# ProPrj__-_AI__2025-12-12.net
KiCad netlist of a schematic drawn in EasyEDA Pro
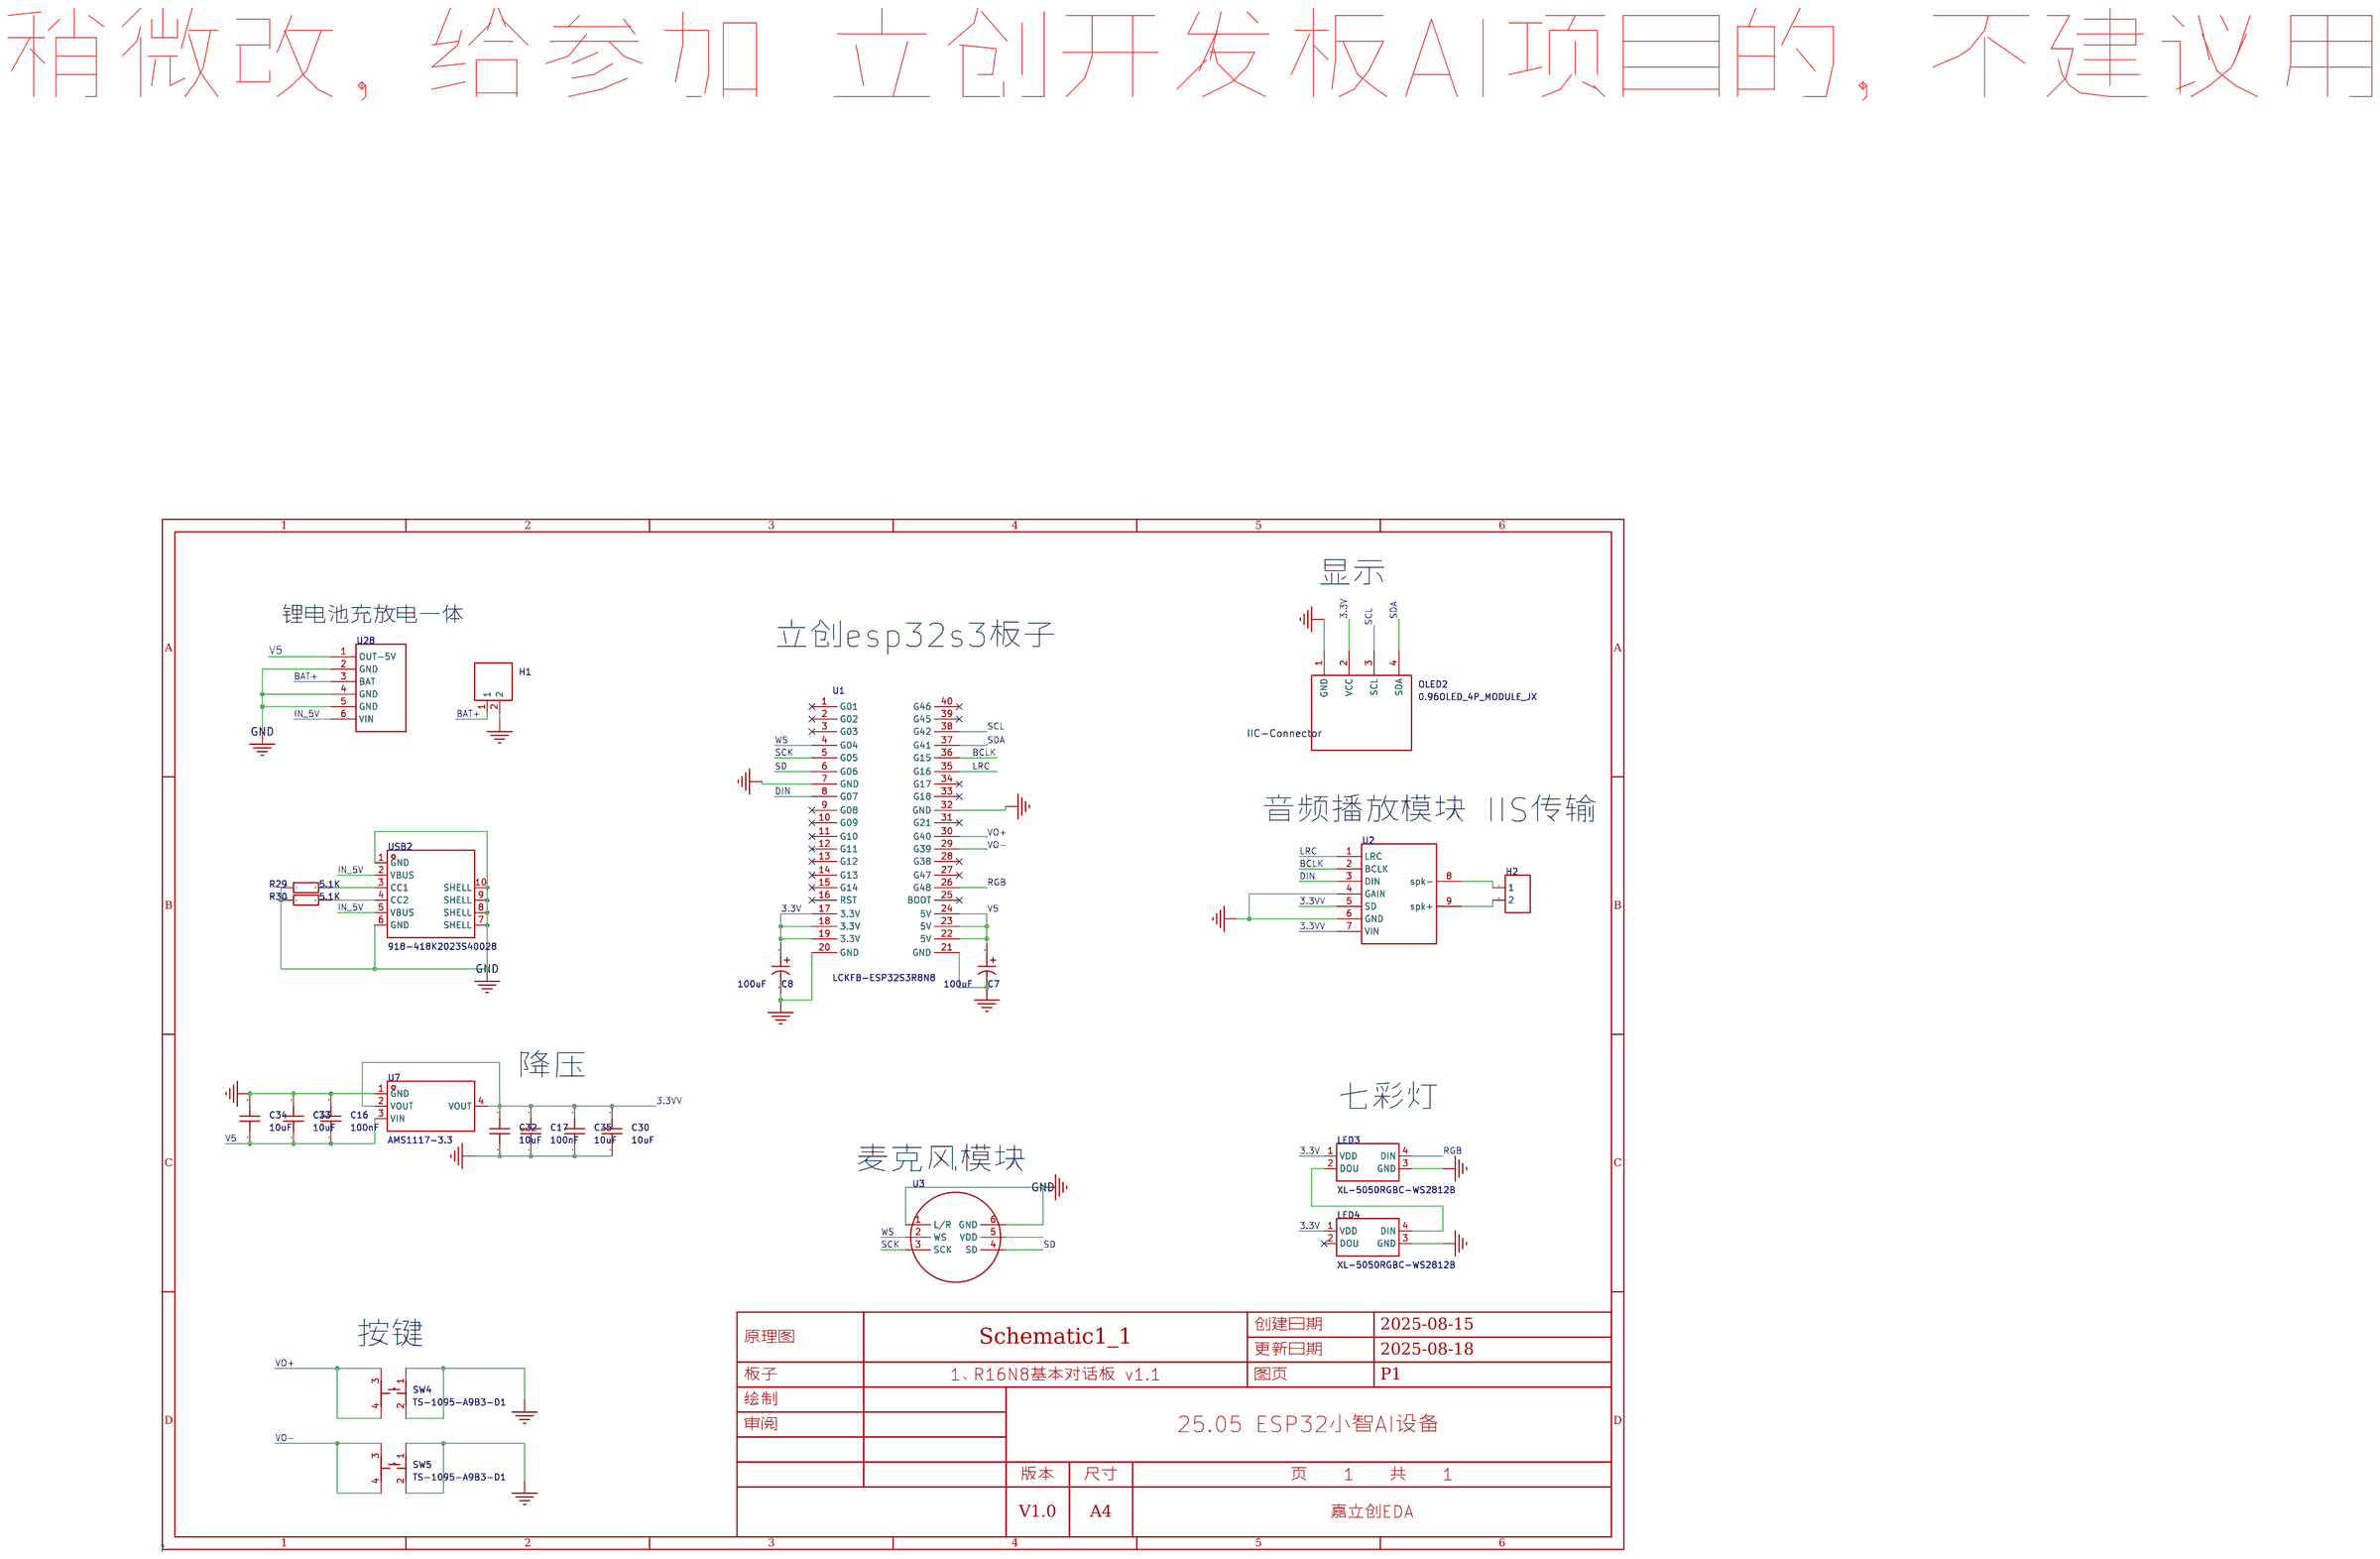
[diagram p0: schematic sheet]

(export (version "E")
  (design (tool "Eeschema 10.0.6"))
  (components
    (comp (ref "C7")
      (value "100uF")
      (footprint "easyedapro:CAP-SMD_BD6.3-L6.6-W6.6-LS7.6-RD")
      (fields (field (name "Manufacturer Part") "RVT1H101M0607") (field (name "Manufacturer") "ROQANG(容强)"))
      (libsource (lib "easyedapro") (part "RVT1H101M0607"))
    )
    (comp (ref "C8")
      (value "100uF")
      (footprint "easyedapro:CAP-SMD_BD6.3-L6.6-W6.6-LS7.6-RD")
      (fields (field (name "Manufacturer Part") "RVT1H101M0607") (field (name "Manufacturer") "ROQANG(容强)"))
      (libsource (lib "easyedapro") (part "RVT1H101M0607"))
    )
    (comp (ref "C16")
      (value "100nF")
      (footprint "easyedapro:C0603")
      (libsource (lib "easyedapro") (part "CapAcitance"))
    )
    (comp (ref "C17")
      (value "100nF")
      (footprint "easyedapro:C0603")
      (libsource (lib "easyedapro") (part "CapAcitance"))
    )
    (comp (ref "C30")
      (value "10uF")
      (footprint "easyedapro:C0603")
      (libsource (lib "easyedapro") (part "CapAcitance"))
    )
    (comp (ref "C32")
      (value "10uF")
      (footprint "easyedapro:C0603")
      (libsource (lib "easyedapro") (part "CapAcitance"))
    )
    (comp (ref "C33")
      (value "10uF")
      (footprint "easyedapro:C0603")
      (libsource (lib "easyedapro") (part "CapAcitance"))
    )
    (comp (ref "C34")
      (value "10uF")
      (footprint "easyedapro:C0603")
      (libsource (lib "easyedapro") (part "CapAcitance"))
    )
    (comp (ref "C35")
      (value "10uF")
      (footprint "easyedapro:C0603")
      (libsource (lib "easyedapro") (part "CapAcitance"))
    )
    (comp (ref "H1")
      (value "B-2100S02P-A110")
      (footprint "easyedapro:HDR-TH_2P-P2.54-V-M-1")
      (fields (field (name "Manufacturer") "Ckmtw(灿科盟)"))
      (libsource (lib "easyedapro") (part "210S-1*2P L=11.6MMGold-plated black"))
    )
    (comp (ref "H2")
      (value "~")
      (footprint "easyedapro:HDR-TH_2P-P2.54-V-F")
      (libsource (lib "easyedapro") (part "Header-Female-2.54_1x2"))
    )
    (comp (ref "LED3")
      (value "XL-5050RGBC-WS2812B")
      (footprint "easyedapro:LED-SMD_4P-L5.0-W5.0-BL_XL-5050RGBC")
      (fields (field (name "Manufacturer") "XINGLIGHT(成兴光)"))
      (libsource (lib "easyedapro") (part "XL-5050RGBC-WS2812B"))
    )
    (comp (ref "LED4")
      (value "XL-5050RGBC-WS2812B")
      (footprint "easyedapro:LED-SMD_4P-L5.0-W5.0-BL_XL-5050RGBC")
      (fields (field (name "Manufacturer") "XINGLIGHT(成兴光)"))
      (libsource (lib "easyedapro") (part "XL-5050RGBC-WS2812B"))
    )
    (comp (ref "OLED2")
      (value "0.96OLED_4P_MODULE_JX")
      (footprint "easyedapro:0.96OLED_4P")
      (libsource (lib "easyedapro") (part "0.96OLED_4P_MODULE_JX"))
    )
    (comp (ref "R29")
      (value "5.1K")
      (footprint "easyedapro:R0603")
      (libsource (lib "easyedapro") (part "电阻"))
    )
    (comp (ref "R30")
      (value "5.1K")
      (footprint "easyedapro:R0603")
      (libsource (lib "easyedapro") (part "电阻"))
    )
    (comp (ref "SW4")
      (value "TS-1095-A9B3-D1")
      (footprint "easyedapro:SW-TH_4P-L6.0-W6.0-P4.50-LS6.5")
      (fields (field (name "Manufacturer") "Yuandi(元迪)"))
      (libsource (lib "easyedapro") (part "TS-1095-A9B3-D1"))
    )
    (comp (ref "SW5")
      (value "TS-1095-A9B3-D1")
      (footprint "easyedapro:SW-TH_4P-L6.0-W6.0-P4.50-LS6.5")
      (fields (field (name "Manufacturer") "Yuandi(元迪)"))
      (libsource (lib "easyedapro") (part "TS-1095-A9B3-D1"))
    )
    (comp (ref "U1")
      (value "LCKFB-ESP32S3R8N8")
      (footprint "easyedapro:DIP-40_L20.32-W51.66-P2.54-LS15.24")
      (fields (field (name "Manufacturer") "立创开发板"))
      (libsource (lib "easyedapro") (part "LCKFB-ESP32S3R8N8"))
    )
    (comp (ref "U2") (value "~") (libsource (lib "easyedapro") (part "MAX98357A")))
    (comp (ref "U3") (value "~") (libsource (lib "easyedapro") (part "INMP441")))
    (comp (ref "U7")
      (value "AMS1117-3.3")
      (footprint "easyedapro:SOT-223-3_L6.5-W3.4-P2.30-LS7.0-BR")
      (fields (field (name "Manufacturer") "AMS"))
      (libsource (lib "easyedapro") (part "AMS1117-3.3"))
    )
    (comp (ref "U28")
      (value "~")
      (footprint "easyedapro:MH-CD42_Module")
      (libsource (lib "easyedapro") (part "mh-cd42"))
    )
    (comp (ref "USB2")
      (value "918-418K2023S40028")
      (footprint "easyedapro:USB-C-SMD_918-418K2023S40026")
      (fields (field (name "Manufacturer") "精拓金"))
      (libsource (lib "easyedapro") (part "918-418K2023S40028"))
    )
  )
  (nets
    (net (code "1") (name "/3.3V") (class "Default")
      (node (ref "C8") (pin "1") (pinfunction "1_1") (pintype "input"))
      (node (ref "LED3") (pin "1") (pinfunction "VDD_1") (pintype "unspecified"))
      (node (ref "LED4") (pin "1") (pinfunction "VDD_1") (pintype "unspecified"))
      (node (ref "OLED2") (pin "2") (pinfunction "VCC_2") (pintype "unspecified"))
      (node (ref "U1") (pin "17") (pinfunction "3.3V_17") (pintype "unspecified"))
      (node (ref "U1") (pin "18") (pinfunction "3.3V_18") (pintype "unspecified"))
      (node (ref "U1") (pin "19") (pinfunction "3.3V_19") (pintype "unspecified"))
    )
    (net (code "2") (name "/3.3VV") (class "Default")
      (node (ref "C17") (pin "2") (pinfunction "2_2") (pintype "input"))
      (node (ref "C30") (pin "2") (pinfunction "2_2") (pintype "input"))
      (node (ref "C32") (pin "2") (pinfunction "2_2") (pintype "input"))
      (node (ref "C35") (pin "2") (pinfunction "2_2") (pintype "input"))
      (node (ref "U2") (pin "5") (pinfunction "SD_5") (pintype "input"))
      (node (ref "U2") (pin "7") (pinfunction "VIN_7") (pintype "input"))
      (node (ref "U7") (pin "2") (pinfunction "VOUT_2") (pintype "unspecified"))
      (node (ref "U7") (pin "4") (pinfunction "VOUT_4") (pintype "unspecified"))
    )
    (net (code "3") (name "/BAT+") (class "Default")
      (node (ref "H1") (pin "1") (pinfunction "1_1") (pintype "unspecified"))
      (node (ref "U28") (pin "3") (pinfunction "BAT_3") (pintype "input"))
    )
    (net (code "4") (name "/BCLK") (class "Default")
      (node (ref "U1") (pin "36") (pinfunction "G15_36") (pintype "unspecified"))
      (node (ref "U2") (pin "2") (pinfunction "BCLK_2") (pintype "input"))
    )
    (net (code "5") (name "/DIN") (class "Default")
      (node (ref "U1") (pin "8") (pinfunction "G07_8") (pintype "unspecified"))
      (node (ref "U2") (pin "3") (pinfunction "DIN_3") (pintype "input"))
    )
    (net (code "6") (name "/IN_5V") (class "Default")
      (node (ref "U28") (pin "6") (pinfunction "VIN_6") (pintype "input"))
      (node (ref "USB2") (pin "2") (pinfunction "VBUS_2") (pintype "unspecified"))
      (node (ref "USB2") (pin "5") (pinfunction "VBUS_5") (pintype "unspecified"))
    )
    (net (code "7") (name "/LRC") (class "Default")
      (node (ref "U1") (pin "35") (pinfunction "G16_35") (pintype "unspecified"))
      (node (ref "U2") (pin "1") (pinfunction "LRC_1") (pintype "input"))
    )
    (net (code "8") (name "/RGB") (class "Default")
      (node (ref "LED3") (pin "4") (pinfunction "DIN_4") (pintype "unspecified"))
      (node (ref "U1") (pin "26") (pinfunction "G48_26") (pintype "unspecified"))
    )
    (net (code "9") (name "/SCK") (class "Default")
      (node (ref "U1") (pin "5") (pinfunction "G05_5") (pintype "unspecified"))
      (node (ref "U3") (pin "3") (pinfunction "SCK_3") (pintype "input"))
    )
    (net (code "10") (name "/SCL") (class "Default")
      (node (ref "OLED2") (pin "3") (pinfunction "SCL_3") (pintype "unspecified"))
      (node (ref "U1") (pin "38") (pinfunction "G42_38") (pintype "unspecified"))
    )
    (net (code "11") (name "/SD") (class "Default")
      (node (ref "U1") (pin "6") (pinfunction "G06_6") (pintype "unspecified"))
      (node (ref "U3") (pin "4") (pinfunction "SD_4") (pintype "input"))
    )
    (net (code "12") (name "/SDA") (class "Default")
      (node (ref "OLED2") (pin "4") (pinfunction "SDA_4") (pintype "unspecified"))
      (node (ref "U1") (pin "37") (pinfunction "G41_37") (pintype "unspecified"))
    )
    (net (code "13") (name "/V5") (class "Default")
      (node (ref "C16") (pin "1") (pinfunction "1_1") (pintype "input"))
      (node (ref "C33") (pin "1") (pinfunction "1_1") (pintype "input"))
      (node (ref "C34") (pin "1") (pinfunction "1_1") (pintype "input"))
      (node (ref "C7") (pin "1") (pinfunction "1_1") (pintype "input"))
      (node (ref "U1") (pin "22") (pinfunction "5V_22") (pintype "unspecified"))
      (node (ref "U1") (pin "23") (pinfunction "5V_23") (pintype "unspecified"))
      (node (ref "U1") (pin "24") (pinfunction "5V_24") (pintype "unspecified"))
      (node (ref "U28") (pin "1") (pinfunction "OUT-5V_1") (pintype "output"))
      (node (ref "U7") (pin "3") (pinfunction "VIN_3") (pintype "unspecified"))
    )
    (net (code "14") (name "/VO+") (class "Default")
      (node (ref "SW4") (pin "3") (pinfunction "3_3") (pintype "unspecified"))
      (node (ref "SW4") (pin "4") (pinfunction "4_4") (pintype "unspecified"))
      (node (ref "U1") (pin "30") (pinfunction "G40_30") (pintype "unspecified"))
    )
    (net (code "15") (name "/VO-") (class "Default")
      (node (ref "SW5") (pin "3") (pinfunction "3_3") (pintype "unspecified"))
      (node (ref "SW5") (pin "4") (pinfunction "4_4") (pintype "unspecified"))
      (node (ref "U1") (pin "29") (pinfunction "G39_29") (pintype "unspecified"))
    )
    (net (code "16") (name "/WS") (class "Default")
      (node (ref "U1") (pin "4") (pinfunction "G04_4") (pintype "unspecified"))
      (node (ref "U3") (pin "2") (pinfunction "WS_2") (pintype "input"))
    )
    (net (code "17") (name "GND") (class "Default")
      (node (ref "C16") (pin "2") (pinfunction "2_2") (pintype "input"))
      (node (ref "C17") (pin "1") (pinfunction "1_1") (pintype "input"))
      (node (ref "C30") (pin "1") (pinfunction "1_1") (pintype "input"))
      (node (ref "C32") (pin "1") (pinfunction "1_1") (pintype "input"))
      (node (ref "C33") (pin "2") (pinfunction "2_2") (pintype "input"))
      (node (ref "C34") (pin "2") (pinfunction "2_2") (pintype "input"))
      (node (ref "C35") (pin "1") (pinfunction "1_1") (pintype "input"))
      (node (ref "C7") (pin "2") (pinfunction "2_2") (pintype "input"))
      (node (ref "C8") (pin "2") (pinfunction "2_2") (pintype "input"))
      (node (ref "H1") (pin "2") (pinfunction "2_2") (pintype "unspecified"))
      (node (ref "LED3") (pin "3") (pinfunction "GND_3") (pintype "unspecified"))
      (node (ref "LED4") (pin "3") (pinfunction "GND_3") (pintype "unspecified"))
      (node (ref "OLED2") (pin "1") (pinfunction "GND_1") (pintype "unspecified"))
      (node (ref "R29") (pin "1") (pinfunction "1_1") (pintype "input"))
      (node (ref "R30") (pin "1") (pinfunction "1_1") (pintype "input"))
      (node (ref "SW4") (pin "1") (pinfunction "1_1") (pintype "unspecified"))
      (node (ref "SW4") (pin "2") (pinfunction "2_2") (pintype "unspecified"))
      (node (ref "SW5") (pin "1") (pinfunction "1_1") (pintype "unspecified"))
      (node (ref "SW5") (pin "2") (pinfunction "2_2") (pintype "unspecified"))
      (node (ref "U1") (pin "20") (pinfunction "GND_20") (pintype "unspecified"))
      (node (ref "U1") (pin "21") (pinfunction "GND_21") (pintype "unspecified"))
      (node (ref "U1") (pin "32") (pinfunction "GND_32") (pintype "unspecified"))
      (node (ref "U1") (pin "7") (pinfunction "GND_7") (pintype "unspecified"))
      (node (ref "U2") (pin "4") (pinfunction "GAIN_4") (pintype "input"))
      (node (ref "U2") (pin "6") (pinfunction "GND_6") (pintype "input"))
      (node (ref "U28") (pin "2") (pinfunction "GND_2") (pintype "input"))
      (node (ref "U28") (pin "4") (pinfunction "GND_4") (pintype "input"))
      (node (ref "U28") (pin "5") (pinfunction "GND_5") (pintype "input"))
      (node (ref "U3") (pin "1") (pinfunction "L/R_1") (pintype "input"))
      (node (ref "U3") (pin "6") (pinfunction "GND_6") (pintype "input"))
      (node (ref "U7") (pin "1") (pinfunction "GND_1") (pintype "unspecified"))
      (node (ref "USB2") (pin "1") (pinfunction "GND_1") (pintype "unspecified"))
      (node (ref "USB2") (pin "10") (pinfunction "SHELL_10") (pintype "unspecified"))
      (node (ref "USB2") (pin "6") (pinfunction "GND_6") (pintype "unspecified"))
      (node (ref "USB2") (pin "7") (pinfunction "SHELL_7") (pintype "unspecified"))
      (node (ref "USB2") (pin "8") (pinfunction "SHELL_8") (pintype "unspecified"))
      (node (ref "USB2") (pin "9") (pinfunction "SHELL_9") (pintype "unspecified"))
    )
    (net (code "18") (name "Net-(LED3-DOU)") (class "Default")
      (node (ref "LED3") (pin "2") (pinfunction "DOU_2") (pintype "unspecified"))
      (node (ref "LED4") (pin "4") (pinfunction "DIN_4") (pintype "unspecified"))
    )
    (net (code "19") (name "Net-(U2-spk+)") (class "Default")
      (node (ref "H2") (pin "2") (pinfunction "2_2") (pintype "input"))
      (node (ref "U2") (pin "9") (pinfunction "spk+_9") (pintype "input"))
    )
    (net (code "20") (name "Net-(U2-spk-)") (class "Default")
      (node (ref "H2") (pin "1") (pinfunction "1_1") (pintype "input"))
      (node (ref "U2") (pin "8") (pinfunction "spk-_8") (pintype "input"))
    )
    (net (code "21") (name "Net-(USB2-CC1)") (class "Default")
      (node (ref "R29") (pin "2") (pinfunction "2_2") (pintype "input"))
      (node (ref "USB2") (pin "3") (pinfunction "CC1_3") (pintype "unspecified"))
    )
    (net (code "22") (name "Net-(USB2-CC2)") (class "Default")
      (node (ref "R30") (pin "2") (pinfunction "2_2") (pintype "input"))
      (node (ref "USB2") (pin "4") (pinfunction "CC2_4") (pintype "unspecified"))
    )
    (net (code "23") (name "unconnected-(LED4-DOU-Pad2)") (class "Default")
      (node (ref "LED4") (pin "2") (pinfunction "DOU_2") (pintype "unspecified+no_connect"))
    )
    (net (code "24") (name "unconnected-(U1-BOOT-Pad25)") (class "Default")
      (node (ref "U1") (pin "25") (pinfunction "BOOT_25") (pintype "unspecified+no_connect"))
    )
    (net (code "25") (name "unconnected-(U1-G01-Pad1)") (class "Default")
      (node (ref "U1") (pin "1") (pinfunction "G01_1") (pintype "unspecified+no_connect"))
    )
    (net (code "26") (name "unconnected-(U1-G02-Pad2)") (class "Default")
      (node (ref "U1") (pin "2") (pinfunction "G02_2") (pintype "unspecified+no_connect"))
    )
    (net (code "27") (name "unconnected-(U1-G03-Pad3)") (class "Default")
      (node (ref "U1") (pin "3") (pinfunction "G03_3") (pintype "unspecified+no_connect"))
    )
    (net (code "28") (name "unconnected-(U1-G08-Pad9)") (class "Default")
      (node (ref "U1") (pin "9") (pinfunction "G08_9") (pintype "unspecified+no_connect"))
    )
    (net (code "29") (name "unconnected-(U1-G09-Pad10)") (class "Default")
      (node (ref "U1") (pin "10") (pinfunction "G09_10") (pintype "unspecified+no_connect"))
    )
    (net (code "30") (name "unconnected-(U1-G10-Pad11)") (class "Default")
      (node (ref "U1") (pin "11") (pinfunction "G10_11") (pintype "unspecified+no_connect"))
    )
    (net (code "31") (name "unconnected-(U1-G11-Pad12)") (class "Default")
      (node (ref "U1") (pin "12") (pinfunction "G11_12") (pintype "unspecified+no_connect"))
    )
    (net (code "32") (name "unconnected-(U1-G12-Pad13)") (class "Default")
      (node (ref "U1") (pin "13") (pinfunction "G12_13") (pintype "unspecified+no_connect"))
    )
    (net (code "33") (name "unconnected-(U1-G13-Pad14)") (class "Default")
      (node (ref "U1") (pin "14") (pinfunction "G13_14") (pintype "unspecified+no_connect"))
    )
    (net (code "34") (name "unconnected-(U1-G14-Pad15)") (class "Default")
      (node (ref "U1") (pin "15") (pinfunction "G14_15") (pintype "unspecified+no_connect"))
    )
    (net (code "35") (name "unconnected-(U1-G17-Pad34)") (class "Default")
      (node (ref "U1") (pin "34") (pinfunction "G17_34") (pintype "unspecified+no_connect"))
    )
    (net (code "36") (name "unconnected-(U1-G18-Pad33)") (class "Default")
      (node (ref "U1") (pin "33") (pinfunction "G18_33") (pintype "unspecified+no_connect"))
    )
    (net (code "37") (name "unconnected-(U1-G21-Pad31)") (class "Default")
      (node (ref "U1") (pin "31") (pinfunction "G21_31") (pintype "unspecified+no_connect"))
    )
    (net (code "38") (name "unconnected-(U1-G38-Pad28)") (class "Default")
      (node (ref "U1") (pin "28") (pinfunction "G38_28") (pintype "unspecified+no_connect"))
    )
    (net (code "39") (name "unconnected-(U1-G45-Pad39)") (class "Default")
      (node (ref "U1") (pin "39") (pinfunction "G45_39") (pintype "unspecified+no_connect"))
    )
    (net (code "40") (name "unconnected-(U1-G46-Pad40)") (class "Default")
      (node (ref "U1") (pin "40") (pinfunction "G46_40") (pintype "unspecified+no_connect"))
    )
    (net (code "41") (name "unconnected-(U1-G47-Pad27)") (class "Default")
      (node (ref "U1") (pin "27") (pinfunction "G47_27") (pintype "unspecified+no_connect"))
    )
    (net (code "42") (name "unconnected-(U1-RST-Pad16)") (class "Default")
      (node (ref "U1") (pin "16") (pinfunction "RST_16") (pintype "unspecified+no_connect"))
    )
    (net (code "43") (name "unconnected-(U3-VDD-Pad5)") (class "Default")
      (node (ref "U3") (pin "5") (pinfunction "VDD_5") (pintype "input"))
    )
  )
)
